# Buck_Boost_Converter.net
KiCad netlist of a schematic drawn in Altium Designer
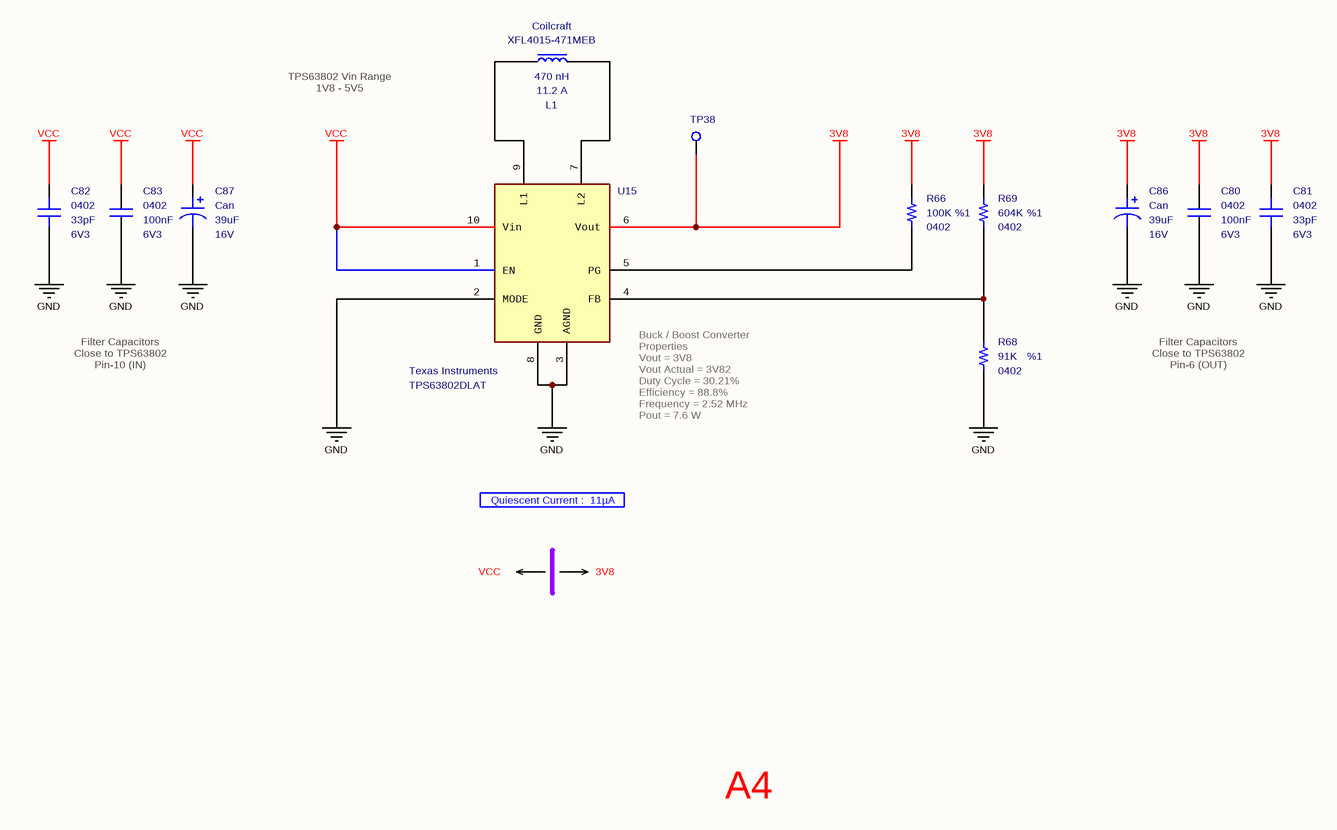
[diagram p0: Buck Boost Converter.SchDoc]

(export (version "E")
  (design (tool "Eeschema 10.0.6"))
  (components
    (comp (ref "C80")
      (value "100nF")
      (footprint "CAPACITOR_0402")
      (description "Capacitor - 100nF [0402-6V3] (Ceramic)")
      (fields
        (field (name "MANUFACTURER_PART_NUMBER") "04026D104KAT4A")
        (field (name "MOUSER_PART_NUMBER") "581-04026D104KAT4A")
        (field (name "CASE") "0402")
        (field (name "VOLTAGE") "6V3")
      )
      (libsource (lib "Ovoo_Schematic") (part "Capacitor - 100nF [0402-6V3]"))
    )
    (comp (ref "C81")
      (value "33pF")
      (footprint "CAPACITOR_0402")
      (description "Capacitor - 33pF [0402] (Ceramic)")
      (fields
        (field (name "MANUFACTURER_PART_NUMBER") "C0402C330J9RACAUTO")
        (field (name "MOUSER_PART_NUMBER") "80-C0402C330J9RAUTO")
        (field (name "CASE") "0402")
        (field (name "VOLTAGE") "6V3")
      )
      (libsource (lib "Ovoo_Schematic") (part "Capacitor - 33pF [0402-6V3]"))
    )
    (comp (ref "C82")
      (value "33pF")
      (footprint "CAPACITOR_0402")
      (description "Capacitor - 33pF [0402] (Ceramic)")
      (fields
        (field (name "MANUFACTURER_PART_NUMBER") "C0402C330J9RACAUTO")
        (field (name "MOUSER_PART_NUMBER") "80-C0402C330J9RAUTO")
        (field (name "CASE") "0402")
        (field (name "VOLTAGE") "6V3")
      )
      (libsource (lib "Ovoo_Schematic") (part "Capacitor - 33pF [0402-6V3]"))
    )
    (comp (ref "C83")
      (value "100nF")
      (footprint "CAPACITOR_0402")
      (description "Capacitor - 100nF [0402-6V3] (Ceramic)")
      (fields
        (field (name "MANUFACTURER_PART_NUMBER") "04026D104KAT4A")
        (field (name "MOUSER_PART_NUMBER") "581-04026D104KAT4A")
        (field (name "CASE") "0402")
        (field (name "VOLTAGE") "6V3")
      )
      (libsource (lib "Ovoo_Schematic") (part "Capacitor - 100nF [0402-6V3]"))
    )
    (comp (ref "C86")
      (value "39uF")
      (footprint "CAPACITOR_CAN-B6")
      (description "Capacitor - 39uF 16V [Can] (Electrolytic)")
      (fields
        (field (name "MANUFACTURER_PART_NUMBER") "16SVPC39MV")
        (field (name "MOUSER_PART_NUMBER") "667-16SVPC39MV")
        (field (name "CASE") "Can")
        (field (name "VOLTAGE") "16V")
      )
      (libsource (lib "Ovoo_Schematic") (part "Capacitor - 39uF [Can-16V]"))
    )
    (comp (ref "C87")
      (value "39uF")
      (footprint "CAPACITOR_CAN-B6")
      (description "Capacitor - 39uF 16V [Can] (Electrolytic)")
      (fields
        (field (name "MANUFACTURER_PART_NUMBER") "16SVPC39MV")
        (field (name "MOUSER_PART_NUMBER") "667-16SVPC39MV")
        (field (name "CASE") "Can")
        (field (name "VOLTAGE") "16V")
      )
      (libsource (lib "Ovoo_Schematic") (part "Capacitor - 39uF [Can-16V]"))
    )
    (comp (ref "L1")
      (value "470 nH")
      (footprint "INDUCTOR_XFL4015")
      (description "Fixed Inductors 0.47uH 20% 11.2A 8.36mOhms AEC-Q200")
      (fields
        (field (name "MOUSER_PART_NUMBER") "994-XFL4015-471MEB")
        (field (name "TOLERANCE") "20%")
        (field (name "MAXIMUM DC CURRENT") "11.2 A")
        (field (name "MANUFACTURER_PART_NUMBER") "XFL4015-471MEB")
        (field (name "MANUFACTURER_NAME") "Coilcraft")
      )
      (libsource (lib "Ovoo_Schematic") (part "Inductor - 470 nH [SMD]"))
    )
    (comp (ref "R66")
      (value "100K")
      (footprint "RESISTOR_0402")
      (description "Thick Film Resistors - SMD 1/16 W 100 Kohms 1%")
      (fields
        (field (name "MANUFACTURER_PART_NUMBER") "CRCW0402100KFKED")
        (field (name "MOUSER_PART_NUMBER") "71-CRCW0402-100K-E3")
        (field (name "TOLERANCE") "%1")
        (field (name "CASE") "0402")
      )
      (libsource (lib "Ovoo_Schematic") (part "Resistor - 100K"))
    )
    (comp (ref "R68")
      (value "91K")
      (footprint "RESISTOR_0402")
      (description "Thick Film Resistors - SMD 1/16 W 91 Kohms 1%")
      (fields
        (field (name "MANUFACTURER_PART_NUMBER") "CRCW040291K0FKED")
        (field (name "MOUSER_PART_NUMBER") "71-CRCW040291K0FKED")
        (field (name "TOLERANCE") "%1")
        (field (name "CASE") "0402")
      )
      (libsource (lib "Ovoo_Schematic") (part "Resistor - 91K"))
    )
    (comp (ref "R69")
      (value "604K")
      (footprint "RESISTOR_0402")
      (description "Thick Film Resistors - SMD 1/16 W 604 Kohms 1%")
      (fields
        (field (name "MANUFACTURER_PART_NUMBER") "CRCW0402604KFKED")
        (field (name "MOUSER_PART_NUMBER") "71-CRCW0402-604K-E3")
        (field (name "TOLERANCE") "%1")
        (field (name "CASE") "0402")
      )
      (libsource (lib "Ovoo_Schematic") (part "Resistor - 604K"))
    )
    (comp (ref "TP38")
      (value "PCB - Test Point")
      (footprint "Test_Pad - Hole")
      (description "Test Point")
      (libsource (lib "Ovoo_Schematic") (part "PCB - Test Point"))
    )
    (comp (ref "U15")
      (value "Buck-Boost Converter")
      (footprint "VSON-10")
      (fields
        (field (name "MOUSER_PART_NUMBER") "595-TPS63802DLAT")
        (field (name "MANUFACTURER_PART_NUMBER") "TPS63802DLAT")
        (field (name "MANUFACTURER_NAME") "Texas Instruments")
      )
      (libsource (lib "Ovoo_Schematic") (part "IC - TPS63802DLAT"))
    )
  )
  (nets
    (net (code "1") (name "3V8") (class "Default")
      (node (ref "C80") (pin "1") (pinfunction "1_1") (pintype "passive"))
      (node (ref "C81") (pin "2") (pinfunction "2_2") (pintype "passive"))
      (node (ref "C86") (pin "1") (pinfunction "1_1") (pintype "passive"))
      (node (ref "R66") (pin "2") (pinfunction "2_2") (pintype "passive"))
      (node (ref "R69") (pin "2") (pinfunction "2_2") (pintype "passive"))
      (node (ref "TP38") (pin "1") (pinfunction "1_1") (pintype "passive"))
      (node (ref "U15") (pin "6") (pinfunction "Vout_6") (pintype "power_in"))
    )
    (net (code "2") (name "GND") (class "Default")
      (node (ref "C80") (pin "2") (pinfunction "2_2") (pintype "passive"))
      (node (ref "C81") (pin "1") (pinfunction "1_1") (pintype "passive"))
      (node (ref "C82") (pin "1") (pinfunction "1_1") (pintype "passive"))
      (node (ref "C83") (pin "2") (pinfunction "2_2") (pintype "passive"))
      (node (ref "C86") (pin "2") (pinfunction "2_2") (pintype "passive"))
      (node (ref "C87") (pin "2") (pinfunction "2_2") (pintype "passive"))
      (node (ref "R68") (pin "1") (pinfunction "1_1") (pintype "passive"))
      (node (ref "U15") (pin "2") (pinfunction "MODE_2") (pintype "passive"))
      (node (ref "U15") (pin "3") (pinfunction "AGND_3") (pintype "power_in"))
      (node (ref "U15") (pin "8") (pinfunction "GND_8") (pintype "power_in"))
    )
    (net (code "3") (name "Net-(U15-FB)") (class "Default")
      (node (ref "R68") (pin "2") (pinfunction "2_2") (pintype "passive"))
      (node (ref "R69") (pin "1") (pinfunction "1_1") (pintype "passive"))
      (node (ref "U15") (pin "4") (pinfunction "FB_4") (pintype "passive"))
    )
    (net (code "4") (name "Net-(U15-L1)") (class "Default")
      (node (ref "L1") (pin "1") (pinfunction "1_1") (pintype "passive"))
      (node (ref "U15") (pin "9") (pinfunction "L1_9") (pintype "passive"))
    )
    (net (code "5") (name "Net-(U15-L2)") (class "Default")
      (node (ref "L1") (pin "2") (pinfunction "2_2") (pintype "passive"))
      (node (ref "U15") (pin "7") (pinfunction "L2_7") (pintype "passive"))
    )
    (net (code "6") (name "Net-(U15-PG)") (class "Default")
      (node (ref "R66") (pin "1") (pinfunction "1_1") (pintype "passive"))
      (node (ref "U15") (pin "5") (pinfunction "PG_5") (pintype "passive"))
    )
    (net (code "7") (name "VCC") (class "Default")
      (node (ref "C82") (pin "2") (pinfunction "2_2") (pintype "passive"))
      (node (ref "C83") (pin "1") (pinfunction "1_1") (pintype "passive"))
      (node (ref "C87") (pin "1") (pinfunction "1_1") (pintype "passive"))
      (node (ref "U15") (pin "1") (pinfunction "EN_1") (pintype "power_in"))
      (node (ref "U15") (pin "10") (pinfunction "Vin_10") (pintype "power_in"))
    )
  )
)
